# SCH_New-Project_2024-05-10.net
KiCad netlist of a schematic drawn in EasyEDA
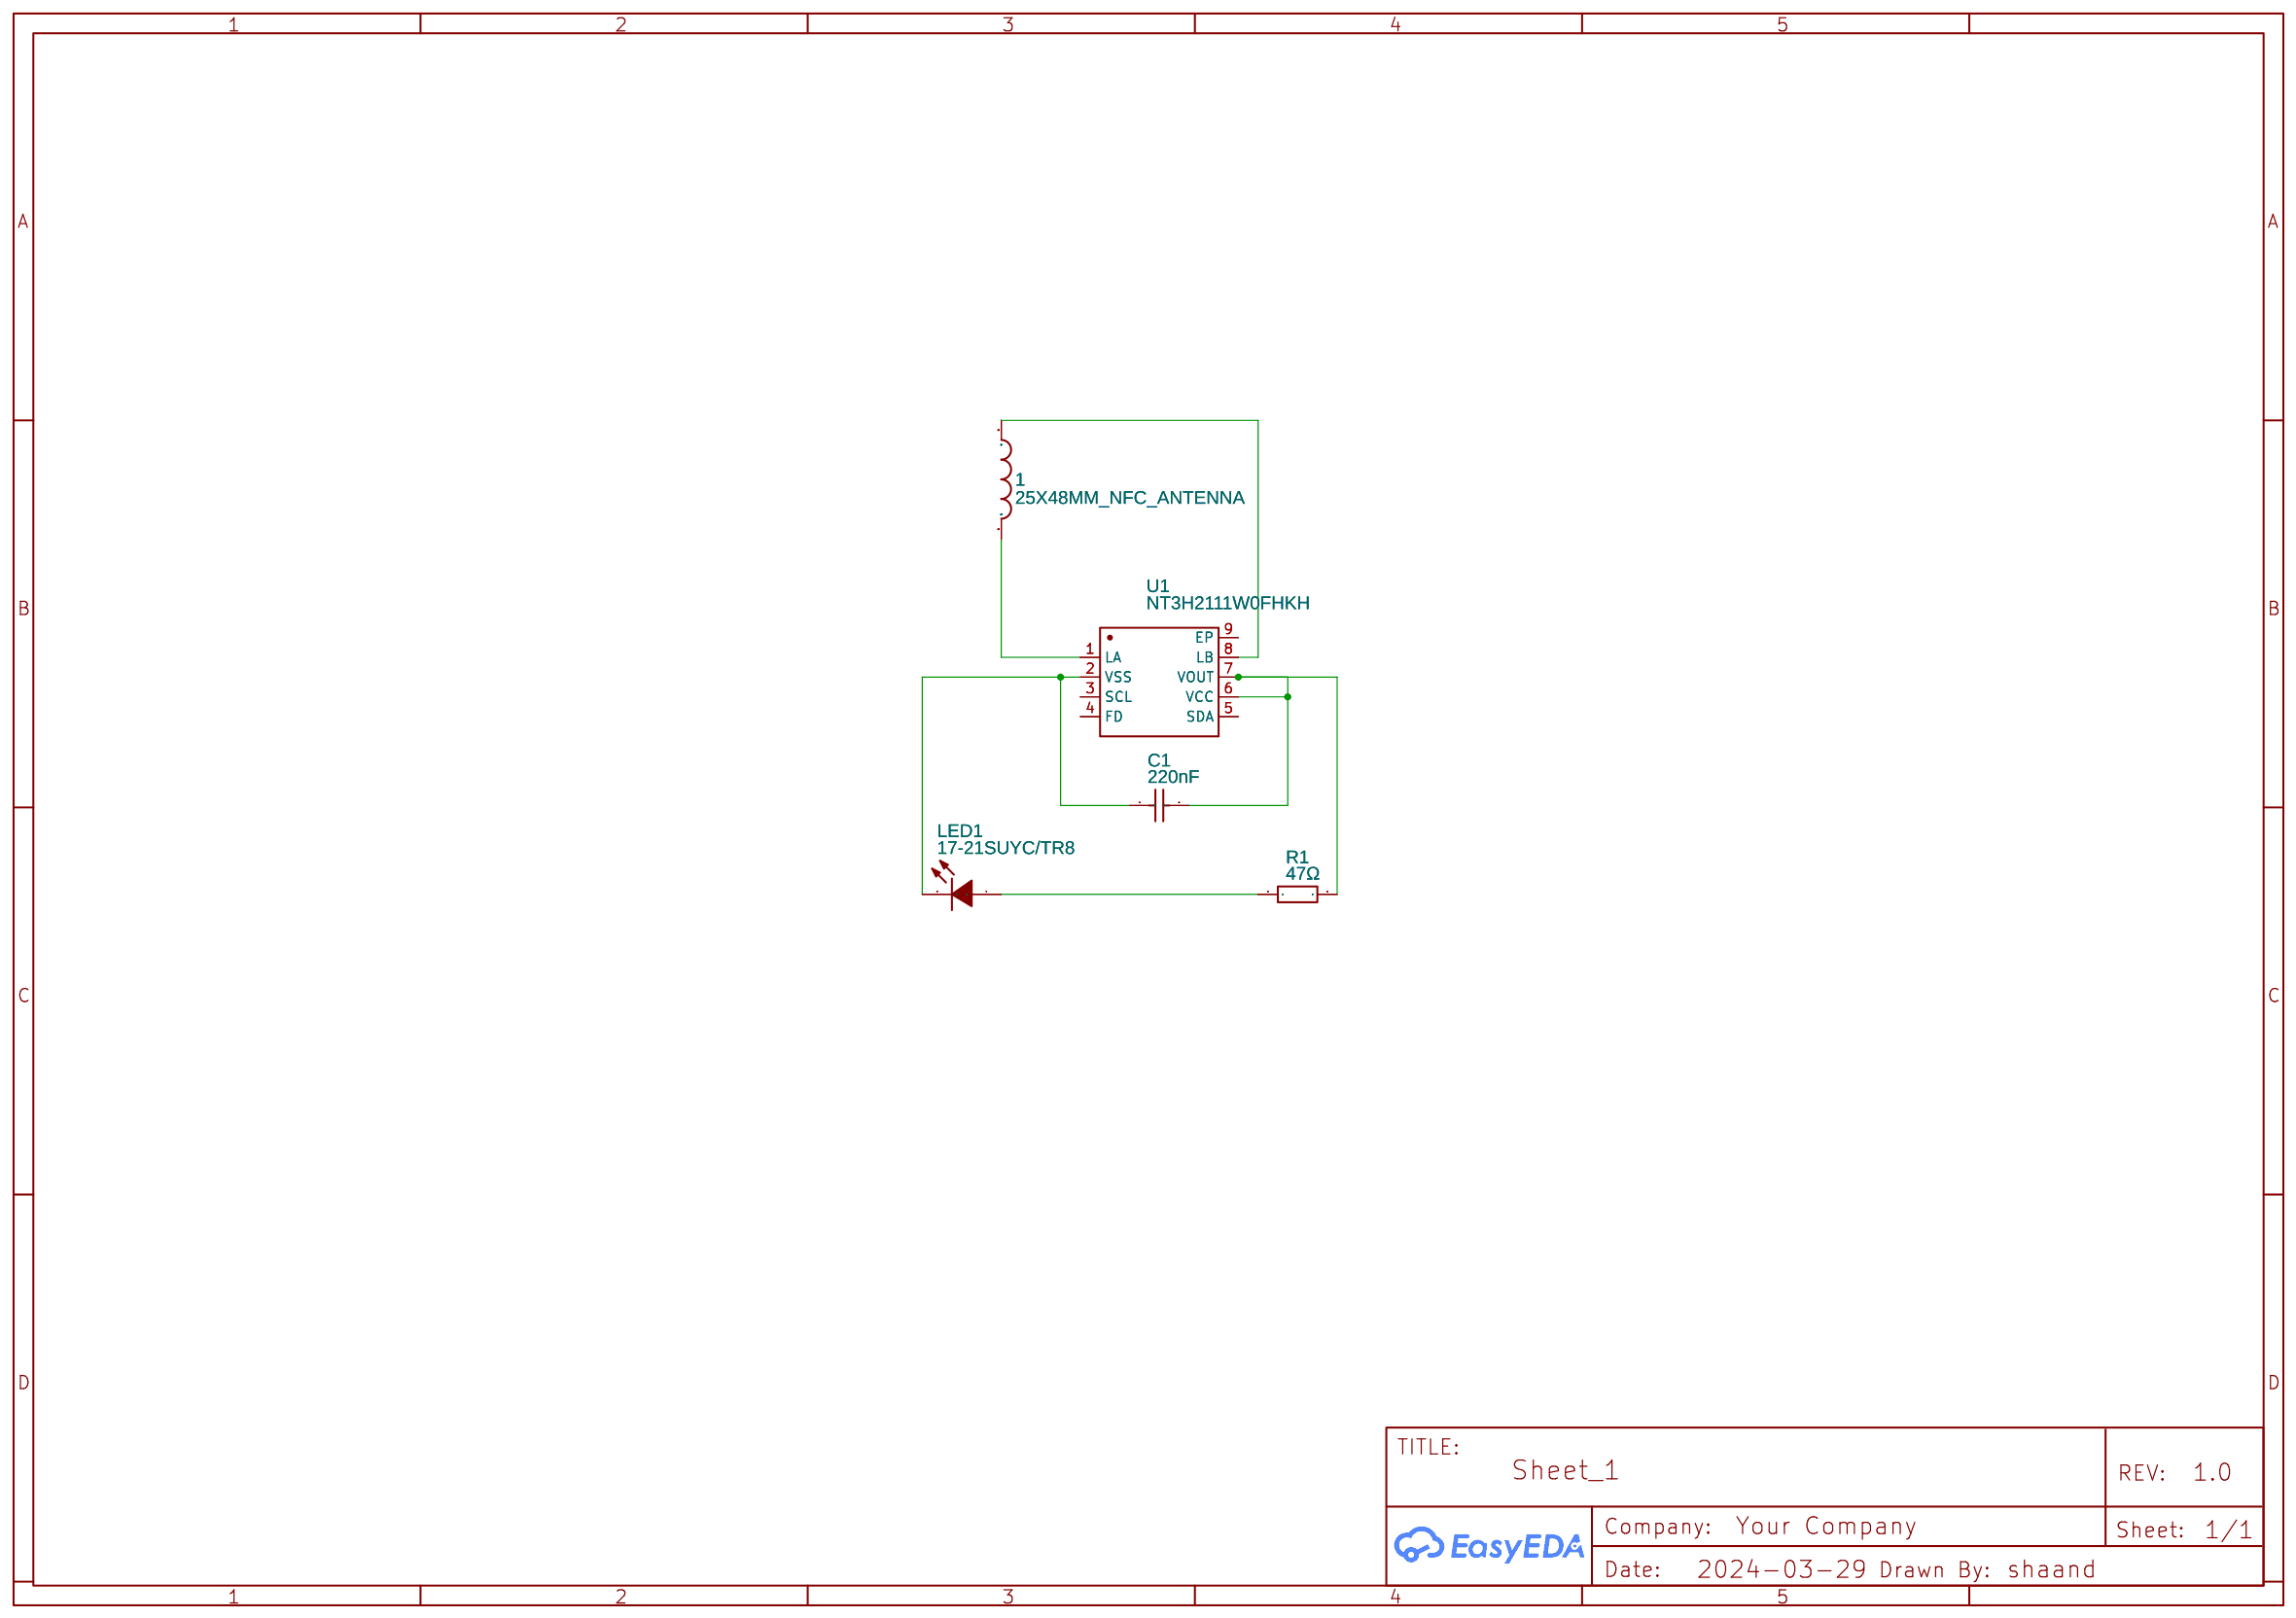
[diagram p0: schematic sheet]

(export (version "E")
  (design (tool "Eeschema 10.0.6"))
  (components
    (comp (ref "1") (value "25X48MM_NFC_ANTENNA") (libsource (lib "") (part "25X48MM_NFC_ANTENNA")))
    (comp (ref "C1")
      (value "220nF")
      (fields
        (field (name "Manufacturer Part") "CL10B224KA8NNNC")
        (field (name "Manufacturer") "SAMSUNG(三星)")
      )
      (libsource (lib "") (part "CL10B224KA8NNNC"))
    )
    (comp (ref "LED1")
      (value "17-21SUYC/TR8")
      (fields (field (name "Manufacturer Part") "KT-0805黄灯") (field (name "Manufacturer") "KENTO"))
      (libsource (lib "") (part "17-21SUYC/TR8"))
    )
    (comp (ref "R1")
      (value "47Ω")
      (fields
        (field (name "Manufacturer Part") "0603WAF470JT5E")
        (field (name "Manufacturer") "UNI-ROYAL(厚声)")
      )
      (libsource (lib "") (part "0603WAF470JT5E"))
    )
    (comp (ref "U1")
      (value "NT3H2111W0FHKH")
      (fields (field (name "Manufacturer") "NXP(恩智浦)"))
      (libsource (lib "") (part "NT3H2111W0FHKH"))
    )
  )
  (nets
    (net (code "1") (name "Net-(LED1-+)") (class "Default")
      (node (ref "LED1") (pin "1") (pinfunction "+_1") (pintype "unspecified"))
      (node (ref "R1") (pin "1") (pinfunction "1_1") (pintype "input"))
    )
    (net (code "2") (name "Net-(LED1--)") (class "Default")
      (node (ref "C1") (pin "1") (pinfunction "1_1") (pintype "input"))
      (node (ref "LED1") (pin "2") (pinfunction "-_2") (pintype "unspecified"))
      (node (ref "U1") (pin "2") (pinfunction "VSS_2") (pintype "unspecified"))
    )
    (net (code "3") (name "Net-(U1-LA)") (class "Default")
      (node (ref "1") (pin "P$2") (pinfunction "P$2_P$2") (pintype "bidirectional"))
      (node (ref "U1") (pin "1") (pinfunction "LA_1") (pintype "unspecified"))
    )
    (net (code "4") (name "Net-(U1-LB)") (class "Default")
      (node (ref "1") (pin "P$1") (pinfunction "P$1_P$1") (pintype "bidirectional"))
      (node (ref "U1") (pin "8") (pinfunction "LB_8") (pintype "unspecified"))
    )
    (net (code "5") (name "Net-(U1-VCC)") (class "Default")
      (node (ref "C1") (pin "2") (pinfunction "2_2") (pintype "input"))
      (node (ref "R1") (pin "2") (pinfunction "2_2") (pintype "input"))
      (node (ref "U1") (pin "6") (pinfunction "VCC_6") (pintype "unspecified"))
      (node (ref "U1") (pin "7") (pinfunction "VOUT_7") (pintype "unspecified"))
    )
    (net (code "6") (name "unconnected-(U1-EP-Pad9)") (class "Default")
      (node (ref "U1") (pin "9") (pinfunction "EP_9") (pintype "unspecified"))
    )
    (net (code "7") (name "unconnected-(U1-FD-Pad4)") (class "Default")
      (node (ref "U1") (pin "4") (pinfunction "FD_4") (pintype "unspecified"))
    )
    (net (code "8") (name "unconnected-(U1-SCL-Pad3)") (class "Default")
      (node (ref "U1") (pin "3") (pinfunction "SCL_3") (pintype "unspecified"))
    )
    (net (code "9") (name "unconnected-(U1-SDA-Pad5)") (class "Default")
      (node (ref "U1") (pin "5") (pinfunction "SDA_5") (pintype "unspecified"))
    )
  )
)
